# PicoBreakout.net
KiCad netlist of a schematic drawn in EAGLE
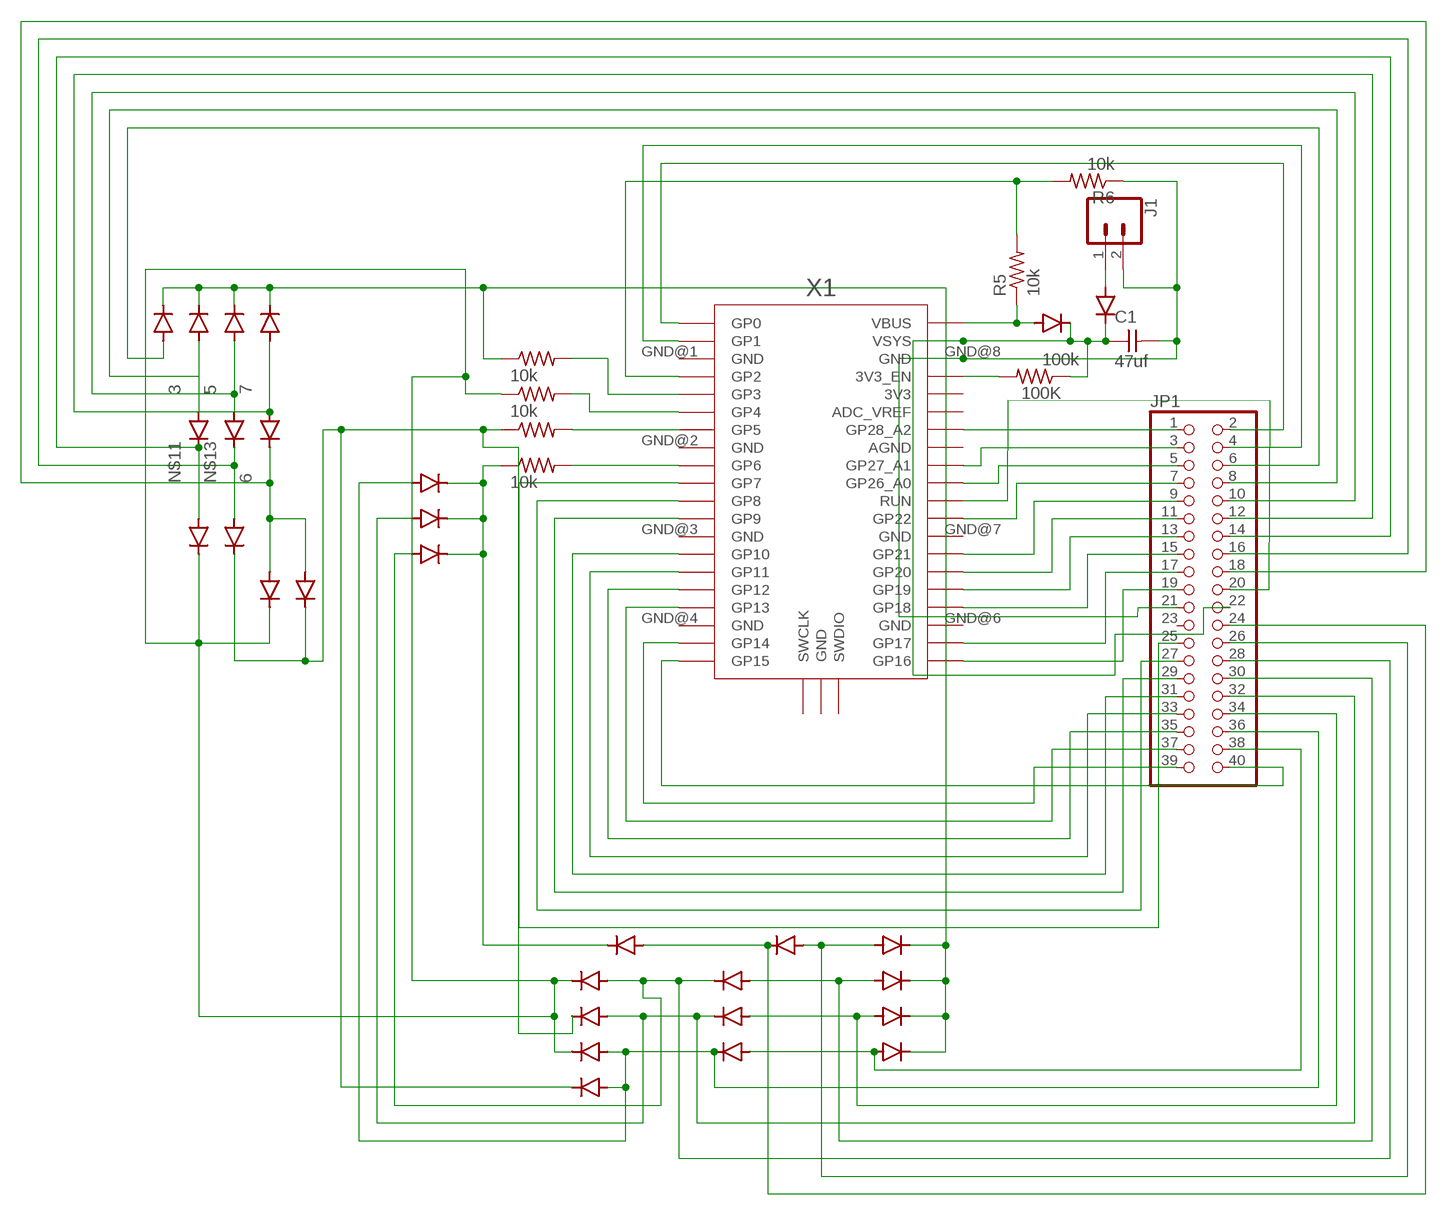
[diagram p0: schematic, sheet 1]

(export (version "E")
  (design (tool "Eeschema 10.0.6"))
  (components
    (comp (ref "100K")
      (value "100k")
      (footprint "eagle-import:R1206FAB")
      (libsource (lib "eagle-import") (part "R1206FAB"))
    )
    (comp (ref "C1")
      (value "47uf")
      (footprint "eagle-import:C1206FAB")
      (libsource (lib "eagle-import") (part "CAP_UNPOLARIZEDFAB"))
    )
    (comp (ref "D1")
      (value "SCHOTTKY")
      (footprint "eagle-import:MINI-SMA")
      (libsource (lib "eagle-import") (part "DIODE_SCHOTTKY_CDBM1100-G"))
    )
    (comp (ref "D2")
      (value "SCHOTTKY")
      (footprint "eagle-import:MINI-SMA")
      (libsource (lib "eagle-import") (part "DIODE_SCHOTTKY_CDBM1100-G"))
    )
    (comp (ref "D3")
      (value "SCHOTTKY")
      (footprint "eagle-import:MINI-SMA")
      (libsource (lib "eagle-import") (part "DIODE_SCHOTTKY_CDBM1100-G"))
    )
    (comp (ref "D4")
      (value "SCHOTTKY")
      (footprint "eagle-import:MINI-SMA")
      (libsource (lib "eagle-import") (part "DIODE_SCHOTTKY_CDBM1100-G"))
    )
    (comp (ref "D5")
      (value "SCHOTTKY")
      (footprint "eagle-import:MINI-SMA")
      (libsource (lib "eagle-import") (part "DIODE_SCHOTTKY_CDBM1100-G"))
    )
    (comp (ref "D6")
      (value "SCHOTTKY")
      (footprint "eagle-import:MINI-SMA")
      (libsource (lib "eagle-import") (part "DIODE_SCHOTTKY_CDBM1100-G"))
    )
    (comp (ref "D7")
      (value "SCHOTTKY")
      (footprint "eagle-import:MINI-SMA")
      (libsource (lib "eagle-import") (part "DIODE_SCHOTTKY_CDBM1100-G"))
    )
    (comp (ref "D8")
      (value "SCHOTTKY")
      (footprint "eagle-import:MINI-SMA")
      (libsource (lib "eagle-import") (part "DIODE_SCHOTTKY_CDBM1100-G"))
    )
    (comp (ref "D9")
      (value "SCHOTTKY")
      (footprint "eagle-import:MINI-SMA")
      (libsource (lib "eagle-import") (part "DIODE_SCHOTTKY_CDBM1100-G"))
    )
    (comp (ref "D10")
      (value "SCHOTTKY")
      (footprint "eagle-import:MINI-SMA")
      (libsource (lib "eagle-import") (part "DIODE_SCHOTTKY_CDBM1100-G"))
    )
    (comp (ref "D11")
      (value "SCHOTTKY")
      (footprint "eagle-import:MINI-SMA")
      (libsource (lib "eagle-import") (part "DIODE_SCHOTTKY_CDBM1100-G"))
    )
    (comp (ref "D12")
      (value "SCHOTTKY")
      (footprint "eagle-import:MINI-SMA")
      (libsource (lib "eagle-import") (part "DIODE_SCHOTTKY_CDBM1100-G"))
    )
    (comp (ref "D13")
      (value "SCHOTTKY")
      (footprint "eagle-import:MINI-SMA")
      (libsource (lib "eagle-import") (part "DIODE_SCHOTTKY_CDBM1100-G"))
    )
    (comp (ref "D14")
      (value "SCHOTTKY")
      (footprint "eagle-import:MINI-SMA")
      (libsource (lib "eagle-import") (part "DIODE_SCHOTTKY_CDBM1100-G"))
    )
    (comp (ref "D15")
      (value "SCHOTTKY")
      (footprint "eagle-import:MINI-SMA")
      (libsource (lib "eagle-import") (part "DIODE_SCHOTTKY_CDBM1100-G"))
    )
    (comp (ref "D16")
      (value "SCHOTTKY")
      (footprint "eagle-import:MINI-SMA")
      (libsource (lib "eagle-import") (part "DIODE_SCHOTTKY_CDBM1100-G"))
    )
    (comp (ref "D17")
      (value "SCHOTTKY")
      (footprint "eagle-import:MINI-SMA")
      (libsource (lib "eagle-import") (part "DIODE_SCHOTTKY_CDBM1100-G"))
    )
    (comp (ref "D18")
      (value "SCHOTTKY")
      (footprint "eagle-import:MINI-SMA")
      (libsource (lib "eagle-import") (part "DIODE_SCHOTTKY_CDBM1100-G"))
    )
    (comp (ref "D19")
      (value "SCHOTTKY")
      (footprint "eagle-import:MINI-SMA")
      (libsource (lib "eagle-import") (part "DIODE_SCHOTTKY_CDBM1100-G"))
    )
    (comp (ref "D20")
      (value "SCHOTTKY")
      (footprint "eagle-import:MINI-SMA")
      (libsource (lib "eagle-import") (part "DIODE_SCHOTTKY_CDBM1100-G"))
    )
    (comp (ref "D21")
      (value "SCHOTTKY")
      (footprint "eagle-import:MINI-SMA")
      (libsource (lib "eagle-import") (part "DIODE_SCHOTTKY_CDBM1100-G"))
    )
    (comp (ref "D22")
      (value "SCHOTTKY")
      (footprint "eagle-import:MINI-SMA")
      (libsource (lib "eagle-import") (part "DIODE_SCHOTTKY_CDBM1100-G"))
    )
    (comp (ref "D23")
      (value "SCHOTTKY")
      (footprint "eagle-import:MINI-SMA")
      (libsource (lib "eagle-import") (part "DIODE_SCHOTTKY_CDBM1100-G"))
    )
    (comp (ref "D24")
      (value "SCHOTTKY")
      (footprint "eagle-import:MINI-SMA")
      (libsource (lib "eagle-import") (part "DIODE_SCHOTTKY_CDBM1100-G"))
    )
    (comp (ref "D25")
      (value "SCHOTTKY")
      (footprint "eagle-import:MINI-SMA")
      (libsource (lib "eagle-import") (part "DIODE_SCHOTTKY_CDBM1100-G"))
    )
    (comp (ref "D26")
      (value "SCHOTTKY")
      (footprint "eagle-import:MINI-SMA")
      (libsource (lib "eagle-import") (part "DIODE_SCHOTTKY_CDBM1100-G"))
    )
    (comp (ref "D27")
      (value "SCHOTTKY")
      (footprint "eagle-import:MINI-SMA")
      (libsource (lib "eagle-import") (part "DIODE_SCHOTTKY_CDBM1100-G"))
    )
    (comp (ref "D28")
      (value "SCHOTTKY")
      (footprint "eagle-import:MINI-SMA")
      (libsource (lib "eagle-import") (part "DIODE_SCHOTTKY_CDBM1100-G"))
    )
    (comp (ref "D29")
      (value "SCHOTTKY")
      (footprint "eagle-import:MINI-SMA")
      (libsource (lib "eagle-import") (part "DIODE_SCHOTTKY_CDBM1100-G"))
    )
    (comp (ref "J1")
      (value "CONN_02LOCK_LONGPADS")
      (footprint "eagle-import:1X02_LOCK_LONGPADS")
      (libsource (lib "eagle-import") (part "CONN_02LOCK_LONGPADS"))
    )
    (comp (ref "JP1")
      (value "PINHD-2X20")
      (footprint "eagle-import:2X20")
      (libsource (lib "eagle-import") (part "PINHD-2X20"))
    )
    (comp (ref "R1")
      (value "10k")
      (footprint "eagle-import:R1206FAB")
      (libsource (lib "eagle-import") (part "R1206FAB"))
    )
    (comp (ref "R2")
      (value "10k")
      (footprint "eagle-import:R1206FAB")
      (libsource (lib "eagle-import") (part "R1206FAB"))
    )
    (comp (ref "R3")
      (value "10k")
      (footprint "eagle-import:R1206FAB")
      (libsource (lib "eagle-import") (part "R1206FAB"))
    )
    (comp (ref "R4")
      (value "10k")
      (footprint "eagle-import:R1206FAB")
      (libsource (lib "eagle-import") (part "R1206FAB"))
    )
    (comp (ref "R5")
      (value "10k")
      (footprint "eagle-import:R1206FAB")
      (libsource (lib "eagle-import") (part "R1206FAB"))
    )
    (comp (ref "R6")
      (value "10k")
      (footprint "eagle-import:R1206FAB")
      (libsource (lib "eagle-import") (part "R1206FAB"))
    )
    (comp (ref "X1")
      (value "RPI_PICO_IG-TH")
      (footprint "eagle-import:RPI_PICO_TH")
      (libsource (lib "eagle-import") (part "RPI_PICO_IG-TH"))
    )
  )
  (nets
    (net (code "1") (name "/3") (class "Default")
      (node (ref "D1") (pin "ANODE") (pinfunction "ANODE_ANODE") (pintype "bidirectional"))
      (node (ref "D4") (pin "ANODE") (pinfunction "ANODE_ANODE") (pintype "bidirectional"))
      (node (ref "JP1") (pin "8") (pinfunction "8_8") (pintype "passive"))
    )
    (net (code "2") (name "/5") (class "Default")
      (node (ref "D2") (pin "ANODE") (pinfunction "ANODE_ANODE") (pintype "bidirectional"))
      (node (ref "D5") (pin "ANODE") (pinfunction "ANODE_ANODE") (pintype "bidirectional"))
      (node (ref "JP1") (pin "10") (pinfunction "10_10") (pintype "passive"))
    )
    (net (code "3") (name "/6") (class "Default")
      (node (ref "D6") (pin "KATHODE") (pinfunction "KATHODE_KATHODE") (pintype "bidirectional"))
      (node (ref "D7") (pin "ANODE") (pinfunction "ANODE_ANODE") (pintype "bidirectional"))
      (node (ref "D8") (pin "ANODE") (pinfunction "ANODE_ANODE") (pintype "bidirectional"))
      (node (ref "JP1") (pin "18") (pinfunction "18_18") (pintype "passive"))
    )
    (net (code "4") (name "/7") (class "Default")
      (node (ref "D3") (pin "ANODE") (pinfunction "ANODE_ANODE") (pintype "bidirectional"))
      (node (ref "D6") (pin "ANODE") (pinfunction "ANODE_ANODE") (pintype "bidirectional"))
      (node (ref "JP1") (pin "12") (pinfunction "12_12") (pintype "passive"))
    )
    (net (code "5") (name "/N$11") (class "Default")
      (node (ref "D25") (pin "ANODE") (pinfunction "ANODE_ANODE") (pintype "bidirectional"))
      (node (ref "D4") (pin "KATHODE") (pinfunction "KATHODE_KATHODE") (pintype "bidirectional"))
      (node (ref "JP1") (pin "14") (pinfunction "14_14") (pintype "passive"))
    )
    (net (code "6") (name "/N$13") (class "Default")
      (node (ref "D27") (pin "ANODE") (pinfunction "ANODE_ANODE") (pintype "bidirectional"))
      (node (ref "D5") (pin "KATHODE") (pinfunction "KATHODE_KATHODE") (pintype "bidirectional"))
      (node (ref "JP1") (pin "16") (pinfunction "16_16") (pintype "passive"))
    )
    (net (code "7") (name "Net-(100K-Pad1)") (class "Default")
      (node (ref "100K") (pin "1") (pinfunction "1_1") (pintype "passive"))
      (node (ref "C1") (pin "1") (pinfunction "1_1") (pintype "passive"))
      (node (ref "D28") (pin "KATHODE") (pinfunction "KATHODE_KATHODE") (pintype "bidirectional"))
      (node (ref "D29") (pin "KATHODE") (pinfunction "KATHODE_KATHODE") (pintype "bidirectional"))
      (node (ref "JP1") (pin "22") (pinfunction "22_22") (pintype "passive"))
      (node (ref "X1") (pin "VSYS") (pinfunction "VSYS_VSYS") (pintype "bidirectional"))
    )
    (net (code "8") (name "Net-(100K-Pad2)") (class "Default")
      (node (ref "100K") (pin "2") (pinfunction "2_2") (pintype "passive"))
      (node (ref "X1") (pin "3V3_EN") (pinfunction "3V3_EN_3V3_EN") (pintype "bidirectional"))
    )
    (net (code "9") (name "Net-(C1-Pad2)") (class "Default")
      (node (ref "C1") (pin "2") (pinfunction "2_2") (pintype "passive"))
      (node (ref "J1") (pin "2") (pinfunction "2_2") (pintype "passive"))
      (node (ref "JP1") (pin "21") (pinfunction "21_21") (pintype "passive"))
      (node (ref "R6") (pin "1") (pinfunction "1_1") (pintype "passive"))
      (node (ref "X1") (pin "GND@8") (pinfunction "GND_GND@8") (pintype "bidirectional"))
    )
    (net (code "10") (name "Net-(D1-PadKATHODE)") (class "Default")
      (node (ref "D1") (pin "KATHODE") (pinfunction "KATHODE_KATHODE") (pintype "bidirectional"))
      (node (ref "D13") (pin "KATHODE") (pinfunction "KATHODE_KATHODE") (pintype "bidirectional"))
      (node (ref "D14") (pin "KATHODE") (pinfunction "KATHODE_KATHODE") (pintype "bidirectional"))
      (node (ref "D15") (pin "KATHODE") (pinfunction "KATHODE_KATHODE") (pintype "bidirectional"))
      (node (ref "D16") (pin "KATHODE") (pinfunction "KATHODE_KATHODE") (pintype "bidirectional"))
      (node (ref "D2") (pin "KATHODE") (pinfunction "KATHODE_KATHODE") (pintype "bidirectional"))
      (node (ref "D24") (pin "KATHODE") (pinfunction "KATHODE_KATHODE") (pintype "bidirectional"))
      (node (ref "D3") (pin "KATHODE") (pinfunction "KATHODE_KATHODE") (pintype "bidirectional"))
      (node (ref "R1") (pin "1") (pinfunction "1_1") (pintype "passive"))
    )
    (net (code "11") (name "Net-(D10-PadANODE)") (class "Default")
      (node (ref "D10") (pin "ANODE") (pinfunction "ANODE_ANODE") (pintype "bidirectional"))
      (node (ref "D14") (pin "ANODE") (pinfunction "ANODE_ANODE") (pintype "bidirectional"))
      (node (ref "JP1") (pin "30") (pinfunction "30_30") (pintype "passive"))
    )
    (net (code "12") (name "Net-(D10-PadKATHODE)") (class "Default")
      (node (ref "D10") (pin "KATHODE") (pinfunction "KATHODE_KATHODE") (pintype "bidirectional"))
      (node (ref "D17") (pin "ANODE") (pinfunction "ANODE_ANODE") (pintype "bidirectional"))
      (node (ref "D23") (pin "ANODE") (pinfunction "ANODE_ANODE") (pintype "bidirectional"))
      (node (ref "JP1") (pin "28") (pinfunction "28_28") (pintype "passive"))
    )
    (net (code "13") (name "Net-(D11-PadANODE)") (class "Default")
      (node (ref "D11") (pin "ANODE") (pinfunction "ANODE_ANODE") (pintype "bidirectional"))
      (node (ref "D15") (pin "ANODE") (pinfunction "ANODE_ANODE") (pintype "bidirectional"))
      (node (ref "JP1") (pin "34") (pinfunction "34_34") (pintype "passive"))
    )
    (net (code "14") (name "Net-(D11-PadKATHODE)") (class "Default")
      (node (ref "D11") (pin "KATHODE") (pinfunction "KATHODE_KATHODE") (pintype "bidirectional"))
      (node (ref "D19") (pin "ANODE") (pinfunction "ANODE_ANODE") (pintype "bidirectional"))
      (node (ref "D22") (pin "ANODE") (pinfunction "ANODE_ANODE") (pintype "bidirectional"))
      (node (ref "JP1") (pin "32") (pinfunction "32_32") (pintype "passive"))
    )
    (net (code "15") (name "Net-(D12-PadANODE)") (class "Default")
      (node (ref "D12") (pin "ANODE") (pinfunction "ANODE_ANODE") (pintype "bidirectional"))
      (node (ref "D16") (pin "ANODE") (pinfunction "ANODE_ANODE") (pintype "bidirectional"))
      (node (ref "JP1") (pin "38") (pinfunction "38_38") (pintype "passive"))
    )
    (net (code "16") (name "Net-(D12-PadKATHODE)") (class "Default")
      (node (ref "D12") (pin "KATHODE") (pinfunction "KATHODE_KATHODE") (pintype "bidirectional"))
      (node (ref "D18") (pin "ANODE") (pinfunction "ANODE_ANODE") (pintype "bidirectional"))
      (node (ref "D20") (pin "ANODE") (pinfunction "ANODE_ANODE") (pintype "bidirectional"))
      (node (ref "D21") (pin "ANODE") (pinfunction "ANODE_ANODE") (pintype "bidirectional"))
      (node (ref "JP1") (pin "36") (pinfunction "36_36") (pintype "passive"))
    )
    (net (code "17") (name "Net-(D13-PadANODE)") (class "Default")
      (node (ref "D13") (pin "ANODE") (pinfunction "ANODE_ANODE") (pintype "bidirectional"))
      (node (ref "D9") (pin "ANODE") (pinfunction "ANODE_ANODE") (pintype "bidirectional"))
      (node (ref "JP1") (pin "26") (pinfunction "26_26") (pintype "passive"))
    )
    (net (code "18") (name "Net-(D17-PadKATHODE)") (class "Default")
      (node (ref "D17") (pin "KATHODE") (pinfunction "KATHODE_KATHODE") (pintype "bidirectional"))
      (node (ref "D18") (pin "KATHODE") (pinfunction "KATHODE_KATHODE") (pintype "bidirectional"))
      (node (ref "D25") (pin "KATHODE") (pinfunction "KATHODE_KATHODE") (pintype "bidirectional"))
      (node (ref "D7") (pin "KATHODE") (pinfunction "KATHODE_KATHODE") (pintype "bidirectional"))
      (node (ref "R2") (pin "1") (pinfunction "1_1") (pintype "passive"))
    )
    (net (code "19") (name "Net-(D19-PadKATHODE)") (class "Default")
      (node (ref "D19") (pin "KATHODE") (pinfunction "KATHODE_KATHODE") (pintype "bidirectional"))
      (node (ref "D20") (pin "KATHODE") (pinfunction "KATHODE_KATHODE") (pintype "bidirectional"))
      (node (ref "D27") (pin "KATHODE") (pinfunction "KATHODE_KATHODE") (pintype "bidirectional"))
      (node (ref "D8") (pin "KATHODE") (pinfunction "KATHODE_KATHODE") (pintype "bidirectional"))
      (node (ref "R3") (pin "1") (pinfunction "1_1") (pintype "passive"))
    )
    (net (code "20") (name "Net-(D21-PadKATHODE)") (class "Default")
      (node (ref "D21") (pin "KATHODE") (pinfunction "KATHODE_KATHODE") (pintype "bidirectional"))
      (node (ref "D22") (pin "KATHODE") (pinfunction "KATHODE_KATHODE") (pintype "bidirectional"))
      (node (ref "D23") (pin "KATHODE") (pinfunction "KATHODE_KATHODE") (pintype "bidirectional"))
      (node (ref "D26") (pin "KATHODE") (pinfunction "KATHODE_KATHODE") (pintype "bidirectional"))
      (node (ref "R4") (pin "1") (pinfunction "1_1") (pintype "passive"))
    )
    (net (code "21") (name "Net-(D24-PadANODE)") (class "Default")
      (node (ref "D24") (pin "ANODE") (pinfunction "ANODE_ANODE") (pintype "bidirectional"))
      (node (ref "JP1") (pin "6") (pinfunction "6_6") (pintype "passive"))
    )
    (net (code "22") (name "Net-(D26-PadANODE)") (class "Default")
      (node (ref "D26") (pin "ANODE") (pinfunction "ANODE_ANODE") (pintype "bidirectional"))
      (node (ref "D9") (pin "KATHODE") (pinfunction "KATHODE_KATHODE") (pintype "bidirectional"))
      (node (ref "JP1") (pin "24") (pinfunction "24_24") (pintype "passive"))
    )
    (net (code "23") (name "Net-(D28-PadANODE)") (class "Default")
      (node (ref "D28") (pin "ANODE") (pinfunction "ANODE_ANODE") (pintype "bidirectional"))
      (node (ref "J1") (pin "1") (pinfunction "1_1") (pintype "passive"))
    )
    (net (code "24") (name "Net-(D29-PadANODE)") (class "Default")
      (node (ref "D29") (pin "ANODE") (pinfunction "ANODE_ANODE") (pintype "bidirectional"))
      (node (ref "R5") (pin "1") (pinfunction "1_1") (pintype "passive"))
      (node (ref "X1") (pin "VBUS") (pinfunction "VBUS_VBUS") (pintype "bidirectional"))
    )
    (net (code "25") (name "Net-(JP1-Pad1)") (class "Default")
      (node (ref "JP1") (pin "1") (pinfunction "1_1") (pintype "passive"))
      (node (ref "X1") (pin "GP28_A2") (pinfunction "GP28_A2_GP28_A2") (pintype "bidirectional"))
    )
    (net (code "26") (name "Net-(JP1-Pad2)") (class "Default")
      (node (ref "JP1") (pin "2") (pinfunction "2_2") (pintype "passive"))
      (node (ref "X1") (pin "GP0") (pinfunction "GP0_GP0") (pintype "bidirectional"))
    )
    (net (code "27") (name "Net-(JP1-Pad3)") (class "Default")
      (node (ref "JP1") (pin "3") (pinfunction "3_3") (pintype "passive"))
      (node (ref "X1") (pin "GP27_A1") (pinfunction "GP27_A1_GP27_A1") (pintype "bidirectional"))
    )
    (net (code "28") (name "Net-(JP1-Pad4)") (class "Default")
      (node (ref "JP1") (pin "4") (pinfunction "4_4") (pintype "passive"))
      (node (ref "X1") (pin "GP1") (pinfunction "GP1_GP1") (pintype "bidirectional"))
    )
    (net (code "29") (name "Net-(JP1-Pad5)") (class "Default")
      (node (ref "JP1") (pin "5") (pinfunction "5_5") (pintype "passive"))
      (node (ref "X1") (pin "GP26_A0") (pinfunction "GP26_A0_GP26_A0") (pintype "bidirectional"))
    )
    (net (code "30") (name "Net-(JP1-Pad7)") (class "Default")
      (node (ref "JP1") (pin "7") (pinfunction "7_7") (pintype "passive"))
      (node (ref "X1") (pin "GP22") (pinfunction "GP22_GP22") (pintype "bidirectional"))
    )
    (net (code "31") (name "Net-(JP1-Pad9)") (class "Default")
      (node (ref "JP1") (pin "9") (pinfunction "9_9") (pintype "passive"))
      (node (ref "X1") (pin "GP21") (pinfunction "GP21_GP21") (pintype "bidirectional"))
    )
    (net (code "32") (name "Net-(JP1-Pad11)") (class "Default")
      (node (ref "JP1") (pin "11") (pinfunction "11_11") (pintype "passive"))
      (node (ref "X1") (pin "GP20") (pinfunction "GP20_GP20") (pintype "bidirectional"))
    )
    (net (code "33") (name "Net-(JP1-Pad13)") (class "Default")
      (node (ref "JP1") (pin "13") (pinfunction "13_13") (pintype "passive"))
      (node (ref "X1") (pin "GP19") (pinfunction "GP19_GP19") (pintype "bidirectional"))
    )
    (net (code "34") (name "Net-(JP1-Pad15)") (class "Default")
      (node (ref "JP1") (pin "15") (pinfunction "15_15") (pintype "passive"))
      (node (ref "X1") (pin "GP18") (pinfunction "GP18_GP18") (pintype "bidirectional"))
    )
    (net (code "35") (name "Net-(JP1-Pad17)") (class "Default")
      (node (ref "JP1") (pin "17") (pinfunction "17_17") (pintype "passive"))
      (node (ref "X1") (pin "GP17") (pinfunction "GP17_GP17") (pintype "bidirectional"))
    )
    (net (code "36") (name "Net-(JP1-Pad19)") (class "Default")
      (node (ref "JP1") (pin "19") (pinfunction "19_19") (pintype "passive"))
      (node (ref "X1") (pin "GP16") (pinfunction "GP16_GP16") (pintype "bidirectional"))
    )
    (net (code "37") (name "Net-(JP1-Pad20)") (class "Default")
      (node (ref "JP1") (pin "20") (pinfunction "20_20") (pintype "passive"))
      (node (ref "X1") (pin "RUN") (pinfunction "RUN_RUN") (pintype "bidirectional"))
    )
    (net (code "38") (name "Net-(JP1-Pad25)") (class "Default")
      (node (ref "JP1") (pin "25") (pinfunction "25_25") (pintype "passive"))
      (node (ref "X1") (pin "GP7") (pinfunction "GP7_GP7") (pintype "bidirectional"))
    )
    (net (code "39") (name "Net-(JP1-Pad27)") (class "Default")
      (node (ref "JP1") (pin "27") (pinfunction "27_27") (pintype "passive"))
      (node (ref "X1") (pin "GP8") (pinfunction "GP8_GP8") (pintype "bidirectional"))
    )
    (net (code "40") (name "Net-(JP1-Pad29)") (class "Default")
      (node (ref "JP1") (pin "29") (pinfunction "29_29") (pintype "passive"))
      (node (ref "X1") (pin "GP9") (pinfunction "GP9_GP9") (pintype "bidirectional"))
    )
    (net (code "41") (name "Net-(JP1-Pad31)") (class "Default")
      (node (ref "JP1") (pin "31") (pinfunction "31_31") (pintype "passive"))
      (node (ref "X1") (pin "GP10") (pinfunction "GP10_GP10") (pintype "bidirectional"))
    )
    (net (code "42") (name "Net-(JP1-Pad33)") (class "Default")
      (node (ref "JP1") (pin "33") (pinfunction "33_33") (pintype "passive"))
      (node (ref "X1") (pin "GP11") (pinfunction "GP11_GP11") (pintype "bidirectional"))
    )
    (net (code "43") (name "Net-(JP1-Pad35)") (class "Default")
      (node (ref "JP1") (pin "35") (pinfunction "35_35") (pintype "passive"))
      (node (ref "X1") (pin "GP12") (pinfunction "GP12_GP12") (pintype "bidirectional"))
    )
    (net (code "44") (name "Net-(JP1-Pad37)") (class "Default")
      (node (ref "JP1") (pin "37") (pinfunction "37_37") (pintype "passive"))
      (node (ref "X1") (pin "GP13") (pinfunction "GP13_GP13") (pintype "bidirectional"))
    )
    (net (code "45") (name "Net-(JP1-Pad39)") (class "Default")
      (node (ref "JP1") (pin "39") (pinfunction "39_39") (pintype "passive"))
      (node (ref "X1") (pin "GP14") (pinfunction "GP14_GP14") (pintype "bidirectional"))
    )
    (net (code "46") (name "Net-(JP1-Pad40)") (class "Default")
      (node (ref "JP1") (pin "40") (pinfunction "40_40") (pintype "passive"))
      (node (ref "X1") (pin "GP15") (pinfunction "GP15_GP15") (pintype "bidirectional"))
    )
    (net (code "47") (name "Net-(R1-Pad2)") (class "Default")
      (node (ref "R1") (pin "2") (pinfunction "2_2") (pintype "passive"))
      (node (ref "X1") (pin "GP3") (pinfunction "GP3_GP3") (pintype "bidirectional"))
    )
    (net (code "48") (name "Net-(R2-Pad2)") (class "Default")
      (node (ref "R2") (pin "2") (pinfunction "2_2") (pintype "passive"))
      (node (ref "X1") (pin "GP4") (pinfunction "GP4_GP4") (pintype "bidirectional"))
    )
    (net (code "49") (name "Net-(R3-Pad2)") (class "Default")
      (node (ref "R3") (pin "2") (pinfunction "2_2") (pintype "passive"))
      (node (ref "X1") (pin "GP5") (pinfunction "GP5_GP5") (pintype "bidirectional"))
    )
    (net (code "50") (name "Net-(R4-Pad2)") (class "Default")
      (node (ref "R4") (pin "2") (pinfunction "2_2") (pintype "passive"))
      (node (ref "X1") (pin "GP6") (pinfunction "GP6_GP6") (pintype "bidirectional"))
    )
    (net (code "51") (name "Net-(R5-Pad2)") (class "Default")
      (node (ref "R5") (pin "2") (pinfunction "2_2") (pintype "passive"))
      (node (ref "R6") (pin "2") (pinfunction "2_2") (pintype "passive"))
      (node (ref "X1") (pin "GP2") (pinfunction "GP2_GP2") (pintype "bidirectional"))
    )
    (net (code "52") (name "unconnected-(JP1-Pad23)") (class "Default")
      (node (ref "JP1") (pin "23") (pinfunction "23_23") (pintype "passive"))
    )
    (net (code "53") (name "unconnected-(X1-GND-PadGND@1)") (class "Default")
      (node (ref "X1") (pin "GND@1") (pinfunction "GND_GND@1") (pintype "bidirectional"))
    )
    (net (code "54") (name "unconnected-(X1-GND-PadGND@2)") (class "Default")
      (node (ref "X1") (pin "GND@2") (pinfunction "GND_GND@2") (pintype "bidirectional"))
    )
    (net (code "55") (name "unconnected-(X1-GND-PadGND@3)") (class "Default")
      (node (ref "X1") (pin "GND@3") (pinfunction "GND_GND@3") (pintype "bidirectional"))
    )
    (net (code "56") (name "unconnected-(X1-GND-PadGND@4)") (class "Default")
      (node (ref "X1") (pin "GND@4") (pinfunction "GND_GND@4") (pintype "bidirectional"))
    )
    (net (code "57") (name "unconnected-(X1-GND-PadGND@5)") (class "Default")
      (node (ref "X1") (pin "GND@5") (pinfunction "GND_GND@5") (pintype "bidirectional"))
    )
    (net (code "58") (name "unconnected-(X1-GND-PadGND@6)") (class "Default")
      (node (ref "X1") (pin "GND@6") (pinfunction "GND_GND@6") (pintype "bidirectional"))
    )
    (net (code "59") (name "unconnected-(X1-GND-PadGND@7)") (class "Default")
      (node (ref "X1") (pin "GND@7") (pinfunction "GND_GND@7") (pintype "bidirectional"))
    )
    (net (code "60") (name "unconnected-(X1-Pad3V3)") (class "Default")
      (node (ref "X1") (pin "3V3") (pinfunction "3V3_3V3") (pintype "bidirectional"))
    )
    (net (code "61") (name "unconnected-(X1-PadADC_VREF)") (class "Default")
      (node (ref "X1") (pin "ADC_VREF") (pinfunction "ADC_VREF_ADC_VREF") (pintype "bidirectional"))
    )
    (net (code "62") (name "unconnected-(X1-PadAGND)") (class "Default")
      (node (ref "X1") (pin "AGND") (pinfunction "AGND_AGND") (pintype "bidirectional"))
    )
    (net (code "63") (name "unconnected-(X1-PadSWCLK)") (class "Default")
      (node (ref "X1") (pin "SWCLK") (pinfunction "SWCLK_SWCLK") (pintype "bidirectional"))
    )
    (net (code "64") (name "unconnected-(X1-PadSWDIO)") (class "Default")
      (node (ref "X1") (pin "SWDIO") (pinfunction "SWDIO_SWDIO") (pintype "bidirectional"))
    )
  )
)
